# Beamersteuerung.net
KiCad netlist of a schematic drawn in EAGLE
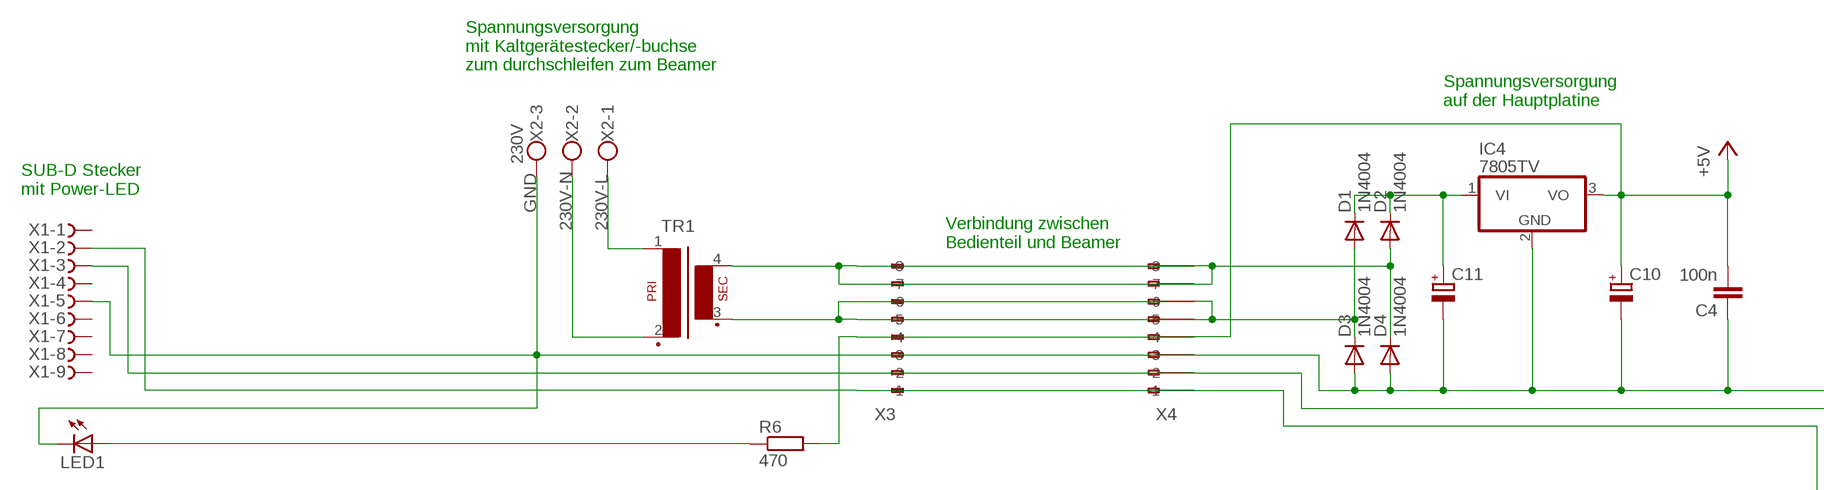
[diagram p0: schematic, sheet 1, part 1 of 2]
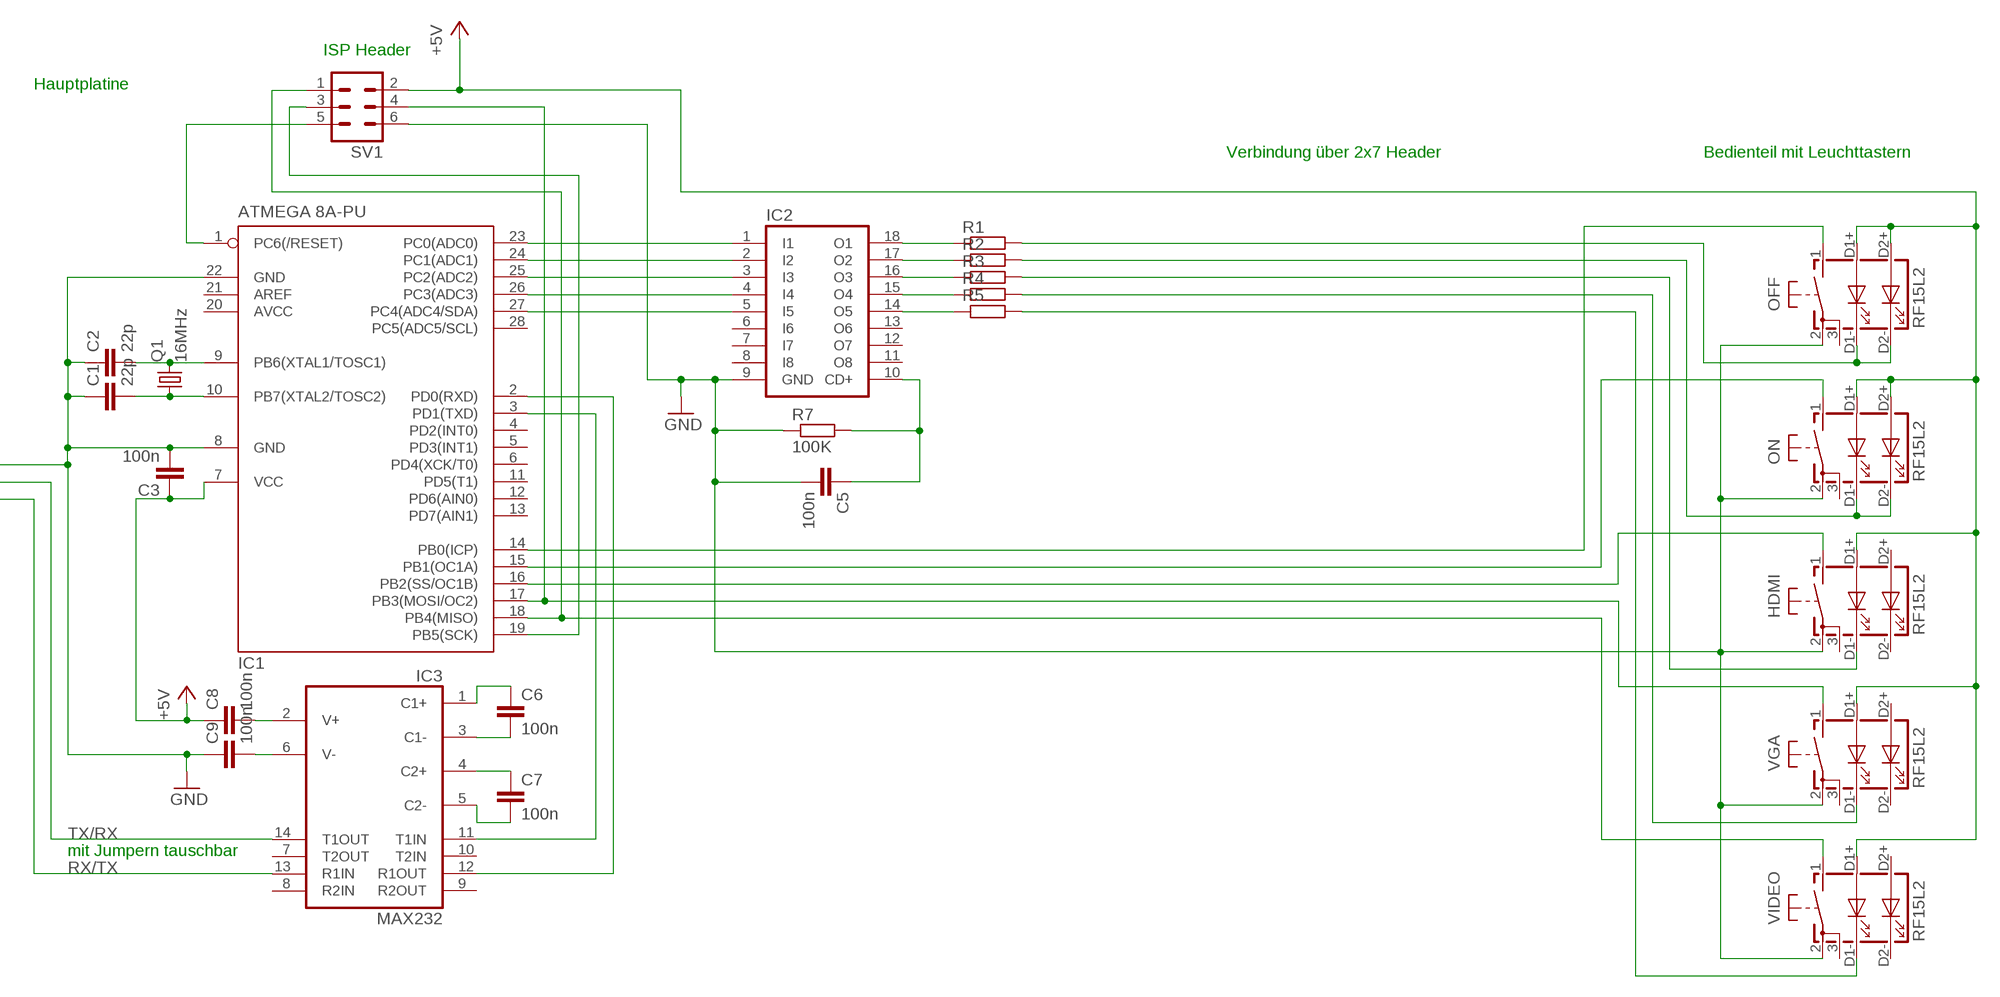
[diagram p1: schematic, sheet 1, part 2 of 2]

(export (version "E")
  (design (tool "Eeschema 10.0.6"))
  (components
    (comp (ref "C1")
      (value "22p")
      (footprint "eagle-import:C025-024X044")
      (libsource (lib "eagle-import") (part "C-EU025-024X044"))
    )
    (comp (ref "C2")
      (value "22p")
      (footprint "eagle-import:C025-024X044")
      (libsource (lib "eagle-import") (part "C-EU025-024X044"))
    )
    (comp (ref "C3")
      (value "100n")
      (footprint "eagle-import:C025-024X044")
      (libsource (lib "eagle-import") (part "C-EU025-024X044"))
    )
    (comp (ref "C4")
      (value "100n")
      (footprint "eagle-import:C025-024X044")
      (libsource (lib "eagle-import") (part "C-EU025-024X044"))
    )
    (comp (ref "C5")
      (value "100n")
      (footprint "eagle-import:C025-024X044")
      (libsource (lib "eagle-import") (part "C-EU025-024X044"))
    )
    (comp (ref "C6")
      (value "100n")
      (footprint "eagle-import:C025-024X044")
      (libsource (lib "eagle-import") (part "C-EU025-024X044"))
    )
    (comp (ref "C7")
      (value "100n")
      (footprint "eagle-import:C025-024X044")
      (libsource (lib "eagle-import") (part "C-EU025-024X044"))
    )
    (comp (ref "C8")
      (value "100n")
      (footprint "eagle-import:C025-024X044")
      (libsource (lib "eagle-import") (part "C-EU025-024X044"))
    )
    (comp (ref "C9")
      (value "100n")
      (footprint "eagle-import:C025-024X044")
      (libsource (lib "eagle-import") (part "C-EU025-024X044"))
    )
    (comp (ref "C10")
      (value "CPOL-EUE2.5-6")
      (footprint "eagle-import:E2,5-6")
      (libsource (lib "eagle-import") (part "CPOL-EUE2.5-6"))
    )
    (comp (ref "C11")
      (value "CPOL-EUE2.5-6")
      (footprint "eagle-import:E2,5-6")
      (libsource (lib "eagle-import") (part "CPOL-EUE2.5-6"))
    )
    (comp (ref "D1")
      (value "1N4004")
      (footprint "eagle-import:DO41-10")
      (libsource (lib "eagle-import") (part "1N4004"))
    )
    (comp (ref "D2")
      (value "1N4004")
      (footprint "eagle-import:DO41-10")
      (libsource (lib "eagle-import") (part "1N4004"))
    )
    (comp (ref "D3")
      (value "1N4004")
      (footprint "eagle-import:DO41-10")
      (libsource (lib "eagle-import") (part "1N4004"))
    )
    (comp (ref "D4")
      (value "1N4004")
      (footprint "eagle-import:DO41-10")
      (libsource (lib "eagle-import") (part "1N4004"))
    )
    (comp (ref "HDMI")
      (value "RF15L2")
      (footprint "eagle-import:RF15L2")
      (libsource (lib "eagle-import") (part "RF15L2"))
    )
    (comp (ref "IC1")
      (value "ATMEGA 8A-PU")
      (footprint "eagle-import:DIL28-3")
      (libsource (lib "eagle-import") (part "MEGA8-P"))
    )
    (comp (ref "IC2")
      (value "ULN2803A")
      (footprint "eagle-import:DIL18")
      (libsource (lib "eagle-import") (part "ULN2803A"))
    )
    (comp (ref "IC3")
      (value "MAX232")
      (footprint "eagle-import:DIL16")
      (fields (field (name "MF") "MAXIM") (field (name "MPN") "MAX232ACPE+"))
      (libsource (lib "eagle-import") (part "MAX232"))
    )
    (comp (ref "IC4")
      (value "7805TV")
      (footprint "eagle-import:TO220V")
      (libsource (lib "eagle-import") (part "78TV05"))
    )
    (comp (ref "LED1")
      (value "LED3MM")
      (footprint "eagle-import:LED3MM")
      (libsource (lib "eagle-import") (part "LED3MM"))
    )
    (comp (ref "OFF")
      (value "RF15L2")
      (footprint "eagle-import:RF15L2")
      (libsource (lib "eagle-import") (part "RF15L2"))
    )
    (comp (ref "ON")
      (value "RF15L2")
      (footprint "eagle-import:RF15L2")
      (libsource (lib "eagle-import") (part "RF15L2"))
    )
    (comp (ref "Q1")
      (value "16MHz")
      (footprint "eagle-import:HC49_S")
      (libsource (lib "eagle-import") (part "CRYSTALHC49S"))
    )
    (comp (ref "R1")
      (value "R-EU_0207/12")
      (footprint "eagle-import:0207_12")
      (libsource (lib "eagle-import") (part "R-EU_0207/12"))
    )
    (comp (ref "R2")
      (value "R-EU_0207/12")
      (footprint "eagle-import:0207_12")
      (libsource (lib "eagle-import") (part "R-EU_0207/12"))
    )
    (comp (ref "R3")
      (value "R-EU_0207/12")
      (footprint "eagle-import:0207_12")
      (libsource (lib "eagle-import") (part "R-EU_0207/12"))
    )
    (comp (ref "R4")
      (value "R-EU_0207/12")
      (footprint "eagle-import:0207_12")
      (libsource (lib "eagle-import") (part "R-EU_0207/12"))
    )
    (comp (ref "R5")
      (value "R-EU_0207/12")
      (footprint "eagle-import:0207_12")
      (libsource (lib "eagle-import") (part "R-EU_0207/12"))
    )
    (comp (ref "R6")
      (value "470")
      (footprint "eagle-import:0207_12")
      (libsource (lib "eagle-import") (part "R-EU_0207/12"))
    )
    (comp (ref "R7")
      (value "100K")
      (footprint "eagle-import:0207_12")
      (libsource (lib "eagle-import") (part "R-EU_0207/12"))
    )
    (comp (ref "SV1")
      (value "ML6")
      (footprint "eagle-import:ML6")
      (libsource (lib "eagle-import") (part "ML6"))
    )
    (comp (ref "TR1")
      (value "VP31")
      (footprint "eagle-import:VP31")
      (libsource (lib "eagle-import") (part "VP31"))
    )
    (comp (ref "VGA")
      (value "RF15L2")
      (footprint "eagle-import:RF15L2")
      (libsource (lib "eagle-import") (part "RF15L2"))
    )
    (comp (ref "VIDEO")
      (value "RF15L2")
      (footprint "eagle-import:RF15L2")
      (libsource (lib "eagle-import") (part "RF15L2"))
    )
    (comp (ref "X1")
      (value "F09VS")
      (footprint "eagle-import:F09V")
      (libsource (lib "eagle-import") (part "F09?SV"))
    )
    (comp (ref "X2")
      (value "230V")
      (footprint "eagle-import:W237-103")
      (fields (field (name "MPN") "237-103"))
      (libsource (lib "eagle-import") (part "W237-103"))
    )
    (comp (ref "X3")
      (value "233-508")
      (footprint "eagle-import:233-508")
      (fields (field (name "MF") "Wago Corporation") (field (name "MPN") "0233-0508"))
      (libsource (lib "eagle-import") (part "233-508"))
    )
    (comp (ref "X4")
      (value "233-508")
      (footprint "eagle-import:233-508")
      (fields (field (name "MF") "Wago Corporation") (field (name "MPN") "0233-0508"))
      (libsource (lib "eagle-import") (part "233-508"))
    )
  )
  (nets
    (net (code "1") (name "+5V") (class "Default")
      (node (ref "C10") (pin "+") (pinfunction "+_+") (pintype "passive"))
      (node (ref "C3") (pin "1") (pinfunction "1_1") (pintype "passive"))
      (node (ref "C4") (pin "2") (pinfunction "2_2") (pintype "passive"))
      (node (ref "C8") (pin "1") (pinfunction "1_1") (pintype "passive"))
      (node (ref "HDMI") (pin "D1+") (pinfunction "A1_D1+") (pintype "passive"))
      (node (ref "IC1") (pin "7") (pinfunction "VCC_7") (pintype "power_in"))
      (node (ref "IC4") (pin "3") (pinfunction "VO_3") (pintype "passive"))
      (node (ref "OFF") (pin "D1+") (pinfunction "A1_D1+") (pintype "passive"))
      (node (ref "OFF") (pin "D2+") (pinfunction "A2_D2+") (pintype "passive"))
      (node (ref "ON") (pin "D1+") (pinfunction "A1_D1+") (pintype "passive"))
      (node (ref "ON") (pin "D2+") (pinfunction "A2_D2+") (pintype "passive"))
      (node (ref "R6") (pin "2") (pinfunction "2_2") (pintype "passive"))
      (node (ref "SV1") (pin "2") (pinfunction "2_2") (pintype "passive"))
      (node (ref "VGA") (pin "D1+") (pinfunction "A1_D1+") (pintype "passive"))
      (node (ref "VIDEO") (pin "D1+") (pinfunction "A1_D1+") (pintype "passive"))
      (node (ref "X3") (pin "A4") (pinfunction "-4_A4") (pintype "passive"))
      (node (ref "X4") (pin "A4") (pinfunction "-4_A4") (pintype "passive"))
    )
    (net (code "2") (name "/230V-L") (class "Default")
      (node (ref "TR1") (pin "1") (pinfunction "P1_1") (pintype "passive"))
      (node (ref "X2") (pin "1") (pinfunction "KL_1") (pintype "passive"))
    )
    (net (code "3") (name "/230V-N") (class "Default")
      (node (ref "TR1") (pin "2") (pinfunction "P2_2") (pintype "passive"))
      (node (ref "X2") (pin "2") (pinfunction "KL_2") (pintype "passive"))
    )
    (net (code "4") (name "/AVCC") (class "Default")
      (node (ref "IC1") (pin "20") (pinfunction "AVCC_20") (pintype "power_in"))
    )
    (net (code "5") (name "/RX{slash}TX") (class "Default")
      (node (ref "IC3") (pin "13") (pinfunction "R1IN_13") (pintype "input"))
      (node (ref "X1") (pin "2") (pinfunction "F_2") (pintype "passive"))
      (node (ref "X3") (pin "A1") (pinfunction "-1_A1") (pintype "passive"))
      (node (ref "X4") (pin "A1") (pinfunction "-1_A1") (pintype "passive"))
    )
    (net (code "6") (name "/TX{slash}RX") (class "Default")
      (node (ref "IC3") (pin "14") (pinfunction "T1OUT_14") (pintype "output"))
      (node (ref "X1") (pin "3") (pinfunction "F_3") (pintype "passive"))
      (node (ref "X3") (pin "A2") (pinfunction "-2_A2") (pintype "passive"))
      (node (ref "X4") (pin "A2") (pinfunction "-2_A2") (pintype "passive"))
    )
    (net (code "7") (name "GND") (class "Default")
      (node (ref "C1") (pin "1") (pinfunction "1_1") (pintype "passive"))
      (node (ref "C10") (pin "-") (pinfunction "-_-") (pintype "passive"))
      (node (ref "C11") (pin "-") (pinfunction "-_-") (pintype "passive"))
      (node (ref "C2") (pin "1") (pinfunction "1_1") (pintype "passive"))
      (node (ref "C3") (pin "2") (pinfunction "2_2") (pintype "passive"))
      (node (ref "C4") (pin "1") (pinfunction "1_1") (pintype "passive"))
      (node (ref "C5") (pin "2") (pinfunction "2_2") (pintype "passive"))
      (node (ref "C9") (pin "1") (pinfunction "1_1") (pintype "passive"))
      (node (ref "D3") (pin "A") (pinfunction "A_A") (pintype "passive"))
      (node (ref "D4") (pin "A") (pinfunction "A_A") (pintype "passive"))
      (node (ref "HDMI") (pin "2") (pinfunction "P_2") (pintype "passive"))
      (node (ref "IC1") (pin "22") (pinfunction "GND_22") (pintype "power_in"))
      (node (ref "IC1") (pin "8") (pinfunction "GND_8") (pintype "power_in"))
      (node (ref "IC2") (pin "9") (pinfunction "GND_9") (pintype "power_in"))
      (node (ref "IC4") (pin "2") (pinfunction "GND_2") (pintype "passive"))
      (node (ref "LED1") (pin "K") (pinfunction "C_K") (pintype "passive"))
      (node (ref "OFF") (pin "2") (pinfunction "P_2") (pintype "passive"))
      (node (ref "ON") (pin "2") (pinfunction "P_2") (pintype "passive"))
      (node (ref "R7") (pin "1") (pinfunction "1_1") (pintype "passive"))
      (node (ref "SV1") (pin "6") (pinfunction "6_6") (pintype "passive"))
      (node (ref "VGA") (pin "2") (pinfunction "P_2") (pintype "passive"))
      (node (ref "VIDEO") (pin "2") (pinfunction "P_2") (pintype "passive"))
      (node (ref "X1") (pin "5") (pinfunction "F_5") (pintype "passive"))
      (node (ref "X2") (pin "3") (pinfunction "KL_3") (pintype "passive"))
      (node (ref "X3") (pin "A3") (pinfunction "-3_A3") (pintype "passive"))
      (node (ref "X4") (pin "A3") (pinfunction "-3_A3") (pintype "passive"))
    )
    (net (code "8") (name "Net-(HDMI-C1)") (class "Default")
      (node (ref "HDMI") (pin "D1-") (pinfunction "C1_D1-") (pintype "passive"))
      (node (ref "R3") (pin "2") (pinfunction "2_2") (pintype "passive"))
    )
    (net (code "9") (name "Net-(HDMI-S)") (class "Default")
      (node (ref "HDMI") (pin "1") (pinfunction "S_1") (pintype "passive"))
      (node (ref "IC1") (pin "16") (pinfunction "PB2(SS/OC1B)_16") (pintype "bidirectional"))
    )
    (net (code "10") (name "Net-(IC1-PB0(ICP))") (class "Default")
      (node (ref "IC1") (pin "14") (pinfunction "PB0(ICP)_14") (pintype "bidirectional"))
      (node (ref "OFF") (pin "1") (pinfunction "S_1") (pintype "passive"))
    )
    (net (code "11") (name "Net-(IC1-PB1(OC1A))") (class "Default")
      (node (ref "IC1") (pin "15") (pinfunction "PB1(OC1A)_15") (pintype "bidirectional"))
      (node (ref "ON") (pin "1") (pinfunction "S_1") (pintype "passive"))
    )
    (net (code "12") (name "Net-(IC1-PB3(MOSI{slash}OC2))") (class "Default")
      (node (ref "IC1") (pin "17") (pinfunction "PB3(MOSI/OC2)_17") (pintype "bidirectional"))
      (node (ref "SV1") (pin "4") (pinfunction "4_4") (pintype "passive"))
      (node (ref "VGA") (pin "1") (pinfunction "S_1") (pintype "passive"))
    )
    (net (code "13") (name "Net-(IC1-PB4(MISO))") (class "Default")
      (node (ref "IC1") (pin "18") (pinfunction "PB4(MISO)_18") (pintype "bidirectional"))
      (node (ref "SV1") (pin "1") (pinfunction "1_1") (pintype "passive"))
      (node (ref "VIDEO") (pin "1") (pinfunction "S_1") (pintype "passive"))
    )
    (net (code "14") (name "Net-(IC1-PB5(SCK))") (class "Default")
      (node (ref "IC1") (pin "19") (pinfunction "PB5(SCK)_19") (pintype "bidirectional"))
      (node (ref "SV1") (pin "3") (pinfunction "3_3") (pintype "passive"))
    )
    (net (code "15") (name "Net-(IC1-PB6(XTAL1{slash}TOSC1))") (class "Default")
      (node (ref "C2") (pin "2") (pinfunction "2_2") (pintype "passive"))
      (node (ref "IC1") (pin "9") (pinfunction "PB6(XTAL1/TOSC1)_9") (pintype "bidirectional"))
      (node (ref "Q1") (pin "2") (pinfunction "2_2") (pintype "passive"))
    )
    (net (code "16") (name "Net-(IC1-PB7(XTAL2{slash}TOSC2))") (class "Default")
      (node (ref "C1") (pin "2") (pinfunction "2_2") (pintype "passive"))
      (node (ref "IC1") (pin "10") (pinfunction "PB7(XTAL2/TOSC2)_10") (pintype "bidirectional"))
      (node (ref "Q1") (pin "1") (pinfunction "1_1") (pintype "passive"))
    )
    (net (code "17") (name "Net-(IC1-PC0(ADC0))") (class "Default")
      (node (ref "IC1") (pin "23") (pinfunction "PC0(ADC0)_23") (pintype "bidirectional"))
      (node (ref "IC2") (pin "1") (pinfunction "I1_1") (pintype "input"))
    )
    (net (code "18") (name "Net-(IC1-PC1(ADC1))") (class "Default")
      (node (ref "IC1") (pin "24") (pinfunction "PC1(ADC1)_24") (pintype "bidirectional"))
      (node (ref "IC2") (pin "2") (pinfunction "I2_2") (pintype "input"))
    )
    (net (code "19") (name "Net-(IC1-PC2(ADC2))") (class "Default")
      (node (ref "IC1") (pin "25") (pinfunction "PC2(ADC2)_25") (pintype "bidirectional"))
      (node (ref "IC2") (pin "3") (pinfunction "I3_3") (pintype "input"))
    )
    (net (code "20") (name "Net-(IC1-PC3(ADC3))") (class "Default")
      (node (ref "IC1") (pin "26") (pinfunction "PC3(ADC3)_26") (pintype "bidirectional"))
      (node (ref "IC2") (pin "4") (pinfunction "I4_4") (pintype "input"))
    )
    (net (code "21") (name "Net-(IC1-PC4(ADC4{slash}SDA))") (class "Default")
      (node (ref "IC1") (pin "27") (pinfunction "PC4(ADC4/SDA)_27") (pintype "bidirectional"))
      (node (ref "IC2") (pin "5") (pinfunction "I5_5") (pintype "input"))
    )
    (net (code "22") (name "Net-(IC1-PC6({slash}RESET))") (class "Default")
      (node (ref "IC1") (pin "1") (pinfunction "PC6(/RESET)_1") (pintype "bidirectional"))
      (node (ref "SV1") (pin "5") (pinfunction "5_5") (pintype "passive"))
    )
    (net (code "23") (name "Net-(IC1-PD0(RXD))") (class "Default")
      (node (ref "IC1") (pin "2") (pinfunction "PD0(RXD)_2") (pintype "bidirectional"))
      (node (ref "IC3") (pin "12") (pinfunction "R1OUT_12") (pintype "output"))
    )
    (net (code "24") (name "Net-(IC1-PD1(TXD))") (class "Default")
      (node (ref "IC1") (pin "3") (pinfunction "PD1(TXD)_3") (pintype "bidirectional"))
      (node (ref "IC3") (pin "11") (pinfunction "T1IN_11") (pintype "input"))
    )
    (net (code "25") (name "Net-(IC2-CD+)") (class "Default")
      (node (ref "C5") (pin "1") (pinfunction "1_1") (pintype "passive"))
      (node (ref "IC2") (pin "10") (pinfunction "CD+_10") (pintype "passive"))
      (node (ref "R7") (pin "2") (pinfunction "2_2") (pintype "passive"))
    )
    (net (code "26") (name "Net-(IC2-O1)") (class "Default")
      (node (ref "IC2") (pin "18") (pinfunction "O1_18") (pintype "open_collector"))
      (node (ref "R1") (pin "1") (pinfunction "1_1") (pintype "passive"))
    )
    (net (code "27") (name "Net-(IC2-O2)") (class "Default")
      (node (ref "IC2") (pin "17") (pinfunction "O2_17") (pintype "open_collector"))
      (node (ref "R2") (pin "1") (pinfunction "1_1") (pintype "passive"))
    )
    (net (code "28") (name "Net-(IC2-O3)") (class "Default")
      (node (ref "IC2") (pin "16") (pinfunction "O3_16") (pintype "open_collector"))
      (node (ref "R3") (pin "1") (pinfunction "1_1") (pintype "passive"))
    )
    (net (code "29") (name "Net-(IC2-O4)") (class "Default")
      (node (ref "IC2") (pin "15") (pinfunction "O4_15") (pintype "open_collector"))
      (node (ref "R4") (pin "1") (pinfunction "1_1") (pintype "passive"))
    )
    (net (code "30") (name "Net-(IC2-O5)") (class "Default")
      (node (ref "IC2") (pin "14") (pinfunction "O5_14") (pintype "open_collector"))
      (node (ref "R5") (pin "1") (pinfunction "1_1") (pintype "passive"))
    )
    (net (code "31") (name "Net-(IC3A-C1+)") (class "Default")
      (node (ref "C6") (pin "1") (pinfunction "1_1") (pintype "passive"))
      (node (ref "IC3") (pin "1") (pinfunction "C1+_1") (pintype "bidirectional"))
    )
    (net (code "32") (name "Net-(IC3A-C1-)") (class "Default")
      (node (ref "C6") (pin "2") (pinfunction "2_2") (pintype "passive"))
      (node (ref "IC3") (pin "3") (pinfunction "C1-_3") (pintype "bidirectional"))
    )
    (net (code "33") (name "Net-(IC3A-C2+)") (class "Default")
      (node (ref "C7") (pin "1") (pinfunction "1_1") (pintype "passive"))
      (node (ref "IC3") (pin "4") (pinfunction "C2+_4") (pintype "bidirectional"))
    )
    (net (code "34") (name "Net-(IC3A-C2-)") (class "Default")
      (node (ref "C7") (pin "2") (pinfunction "2_2") (pintype "passive"))
      (node (ref "IC3") (pin "5") (pinfunction "C2-_5") (pintype "bidirectional"))
    )
    (net (code "35") (name "Net-(IC3A-V+)") (class "Default")
      (node (ref "C8") (pin "2") (pinfunction "2_2") (pintype "passive"))
      (node (ref "IC3") (pin "2") (pinfunction "V+_2") (pintype "bidirectional"))
    )
    (net (code "36") (name "Net-(IC3A-V-)") (class "Default")
      (node (ref "C9") (pin "2") (pinfunction "2_2") (pintype "passive"))
      (node (ref "IC3") (pin "6") (pinfunction "V-_6") (pintype "bidirectional"))
    )
    (net (code "37") (name "Net-(IC4-VI)") (class "Default")
      (node (ref "C11") (pin "+") (pinfunction "+_+") (pintype "passive"))
      (node (ref "D1") (pin "C") (pinfunction "C_C") (pintype "passive"))
      (node (ref "D2") (pin "C") (pinfunction "C_C") (pintype "passive"))
      (node (ref "IC4") (pin "1") (pinfunction "VI_1") (pintype "input"))
    )
    (net (code "38") (name "Net-(LED1-PadA)") (class "Default")
      (node (ref "LED1") (pin "A") (pinfunction "A_A") (pintype "passive"))
      (node (ref "R6") (pin "1") (pinfunction "1_1") (pintype "passive"))
    )
    (net (code "39") (name "Net-(OFF-C1)") (class "Default")
      (node (ref "OFF") (pin "D1-") (pinfunction "C1_D1-") (pintype "passive"))
      (node (ref "OFF") (pin "D2-") (pinfunction "C2_D2-") (pintype "passive"))
      (node (ref "R1") (pin "2") (pinfunction "2_2") (pintype "passive"))
    )
    (net (code "40") (name "Net-(ON-C1)") (class "Default")
      (node (ref "ON") (pin "D1-") (pinfunction "C1_D1-") (pintype "passive"))
      (node (ref "ON") (pin "D2-") (pinfunction "C2_D2-") (pintype "passive"))
      (node (ref "R2") (pin "2") (pinfunction "2_2") (pintype "passive"))
    )
    (net (code "41") (name "Net-(TR1-S3)") (class "Default")
      (node (ref "D1") (pin "A") (pinfunction "A_A") (pintype "passive"))
      (node (ref "D3") (pin "C") (pinfunction "C_C") (pintype "passive"))
      (node (ref "TR1") (pin "3") (pinfunction "S3_3") (pintype "passive"))
      (node (ref "X3") (pin "A5") (pinfunction "-5_A5") (pintype "passive"))
      (node (ref "X3") (pin "A6") (pinfunction "-6_A6") (pintype "passive"))
      (node (ref "X4") (pin "A5") (pinfunction "-5_A5") (pintype "passive"))
      (node (ref "X4") (pin "A6") (pinfunction "-6_A6") (pintype "passive"))
    )
    (net (code "42") (name "Net-(TR1-S4)") (class "Default")
      (node (ref "D2") (pin "A") (pinfunction "A_A") (pintype "passive"))
      (node (ref "D4") (pin "C") (pinfunction "C_C") (pintype "passive"))
      (node (ref "TR1") (pin "4") (pinfunction "S4_4") (pintype "passive"))
      (node (ref "X3") (pin "A7") (pinfunction "-7_A7") (pintype "passive"))
      (node (ref "X3") (pin "A8") (pinfunction "-8_A8") (pintype "passive"))
      (node (ref "X4") (pin "A7") (pinfunction "-7_A7") (pintype "passive"))
      (node (ref "X4") (pin "A8") (pinfunction "-8_A8") (pintype "passive"))
    )
    (net (code "43") (name "Net-(VGA-C1)") (class "Default")
      (node (ref "R4") (pin "2") (pinfunction "2_2") (pintype "passive"))
      (node (ref "VGA") (pin "D1-") (pinfunction "C1_D1-") (pintype "passive"))
    )
    (net (code "44") (name "Net-(VIDEO-C1)") (class "Default")
      (node (ref "R5") (pin "2") (pinfunction "2_2") (pintype "passive"))
      (node (ref "VIDEO") (pin "D1-") (pinfunction "C1_D1-") (pintype "passive"))
    )
    (net (code "45") (name "unconnected-(HDMI-A2-PadD2+)") (class "Default")
      (node (ref "HDMI") (pin "D2+") (pinfunction "A2_D2+") (pintype "passive"))
    )
    (net (code "46") (name "unconnected-(HDMI-C2-PadD2-)") (class "Default")
      (node (ref "HDMI") (pin "D2-") (pinfunction "C2_D2-") (pintype "passive"))
    )
    (net (code "47") (name "unconnected-(HDMI-P-Pad3)") (class "Default")
      (node (ref "HDMI") (pin "3") (pinfunction "P_3") (pintype "passive"))
    )
    (net (code "48") (name "unconnected-(IC1-AREF-Pad21)") (class "Default")
      (node (ref "IC1") (pin "21") (pinfunction "AREF_21") (pintype "passive"))
    )
    (net (code "49") (name "unconnected-(IC1-PC5(ADC5{slash}SCL)-Pad28)") (class "Default")
      (node (ref "IC1") (pin "28") (pinfunction "PC5(ADC5/SCL)_28") (pintype "bidirectional"))
    )
    (net (code "50") (name "unconnected-(IC1-PD2(INT0)-Pad4)") (class "Default")
      (node (ref "IC1") (pin "4") (pinfunction "PD2(INT0)_4") (pintype "bidirectional"))
    )
    (net (code "51") (name "unconnected-(IC1-PD3(INT1)-Pad5)") (class "Default")
      (node (ref "IC1") (pin "5") (pinfunction "PD3(INT1)_5") (pintype "bidirectional"))
    )
    (net (code "52") (name "unconnected-(IC1-PD4(XCK{slash}T0)-Pad6)") (class "Default")
      (node (ref "IC1") (pin "6") (pinfunction "PD4(XCK/T0)_6") (pintype "bidirectional"))
    )
    (net (code "53") (name "unconnected-(IC1-PD5(T1)-Pad11)") (class "Default")
      (node (ref "IC1") (pin "11") (pinfunction "PD5(T1)_11") (pintype "bidirectional"))
    )
    (net (code "54") (name "unconnected-(IC1-PD6(AIN0)-Pad12)") (class "Default")
      (node (ref "IC1") (pin "12") (pinfunction "PD6(AIN0)_12") (pintype "bidirectional"))
    )
    (net (code "55") (name "unconnected-(IC1-PD7(AIN1)-Pad13)") (class "Default")
      (node (ref "IC1") (pin "13") (pinfunction "PD7(AIN1)_13") (pintype "bidirectional"))
    )
    (net (code "56") (name "unconnected-(IC2-I6-Pad6)") (class "Default")
      (node (ref "IC2") (pin "6") (pinfunction "I6_6") (pintype "input"))
    )
    (net (code "57") (name "unconnected-(IC2-I7-Pad7)") (class "Default")
      (node (ref "IC2") (pin "7") (pinfunction "I7_7") (pintype "input"))
    )
    (net (code "58") (name "unconnected-(IC2-I8-Pad8)") (class "Default")
      (node (ref "IC2") (pin "8") (pinfunction "I8_8") (pintype "input"))
    )
    (net (code "59") (name "unconnected-(IC2-O6-Pad13)") (class "Default")
      (node (ref "IC2") (pin "13") (pinfunction "O6_13") (pintype "open_collector"))
    )
    (net (code "60") (name "unconnected-(IC2-O7-Pad12)") (class "Default")
      (node (ref "IC2") (pin "12") (pinfunction "O7_12") (pintype "open_collector"))
    )
    (net (code "61") (name "unconnected-(IC2-O8-Pad11)") (class "Default")
      (node (ref "IC2") (pin "11") (pinfunction "O8_11") (pintype "open_collector"))
    )
    (net (code "62") (name "unconnected-(IC3A-R2IN-Pad8)") (class "Default")
      (node (ref "IC3") (pin "8") (pinfunction "R2IN_8") (pintype "input"))
    )
    (net (code "63") (name "unconnected-(IC3A-R2OUT-Pad9)") (class "Default")
      (node (ref "IC3") (pin "9") (pinfunction "R2OUT_9") (pintype "output"))
    )
    (net (code "64") (name "unconnected-(IC3A-T2IN-Pad10)") (class "Default")
      (node (ref "IC3") (pin "10") (pinfunction "T2IN_10") (pintype "input"))
    )
    (net (code "65") (name "unconnected-(IC3A-T2OUT-Pad7)") (class "Default")
      (node (ref "IC3") (pin "7") (pinfunction "T2OUT_7") (pintype "output"))
    )
    (net (code "66") (name "unconnected-(OFF-P-Pad3)") (class "Default")
      (node (ref "OFF") (pin "3") (pinfunction "P_3") (pintype "passive"))
    )
    (net (code "67") (name "unconnected-(ON-P-Pad3)") (class "Default")
      (node (ref "ON") (pin "3") (pinfunction "P_3") (pintype "passive"))
    )
    (net (code "68") (name "unconnected-(VGA-A2-PadD2+)") (class "Default")
      (node (ref "VGA") (pin "D2+") (pinfunction "A2_D2+") (pintype "passive"))
    )
    (net (code "69") (name "unconnected-(VGA-C2-PadD2-)") (class "Default")
      (node (ref "VGA") (pin "D2-") (pinfunction "C2_D2-") (pintype "passive"))
    )
    (net (code "70") (name "unconnected-(VGA-P-Pad3)") (class "Default")
      (node (ref "VGA") (pin "3") (pinfunction "P_3") (pintype "passive"))
    )
    (net (code "71") (name "unconnected-(VIDEO-A2-PadD2+)") (class "Default")
      (node (ref "VIDEO") (pin "D2+") (pinfunction "A2_D2+") (pintype "passive"))
    )
    (net (code "72") (name "unconnected-(VIDEO-C2-PadD2-)") (class "Default")
      (node (ref "VIDEO") (pin "D2-") (pinfunction "C2_D2-") (pintype "passive"))
    )
    (net (code "73") (name "unconnected-(VIDEO-P-Pad3)") (class "Default")
      (node (ref "VIDEO") (pin "3") (pinfunction "P_3") (pintype "passive"))
    )
    (net (code "74") (name "unconnected-(X1A-F-Pad1)") (class "Default")
      (node (ref "X1") (pin "1") (pinfunction "F_1") (pintype "passive"))
    )
    (net (code "75") (name "unconnected-(X1D-F-Pad4)") (class "Default")
      (node (ref "X1") (pin "4") (pinfunction "F_4") (pintype "passive"))
    )
    (net (code "76") (name "unconnected-(X1F-F-Pad6)") (class "Default")
      (node (ref "X1") (pin "6") (pinfunction "F_6") (pintype "passive"))
    )
    (net (code "77") (name "unconnected-(X1G-F-Pad7)") (class "Default")
      (node (ref "X1") (pin "7") (pinfunction "F_7") (pintype "passive"))
    )
    (net (code "78") (name "unconnected-(X1H-F-Pad8)") (class "Default")
      (node (ref "X1") (pin "8") (pinfunction "F_8") (pintype "passive"))
    )
    (net (code "79") (name "unconnected-(X1I-F-Pad9)") (class "Default")
      (node (ref "X1") (pin "9") (pinfunction "F_9") (pintype "passive"))
    )
    (net (code "80") (name "unconnected-(X3-B-1-PadB1)") (class "Default")
      (node (ref "X3") (pin "B1") (pinfunction "B-1_B1") (pintype "passive"))
    )
    (net (code "81") (name "unconnected-(X3-B-2-PadB2)") (class "Default")
      (node (ref "X3") (pin "B2") (pinfunction "B-2_B2") (pintype "passive"))
    )
    (net (code "82") (name "unconnected-(X3-B-3-PadB3)") (class "Default")
      (node (ref "X3") (pin "B3") (pinfunction "B-3_B3") (pintype "passive"))
    )
    (net (code "83") (name "unconnected-(X3-B-4-PadB4)") (class "Default")
      (node (ref "X3") (pin "B4") (pinfunction "B-4_B4") (pintype "passive"))
    )
    (net (code "84") (name "unconnected-(X3-B-5-PadB5)") (class "Default")
      (node (ref "X3") (pin "B5") (pinfunction "B-5_B5") (pintype "passive"))
    )
    (net (code "85") (name "unconnected-(X3-B-6-PadB6)") (class "Default")
      (node (ref "X3") (pin "B6") (pinfunction "B-6_B6") (pintype "passive"))
    )
    (net (code "86") (name "unconnected-(X3-B-7-PadB7)") (class "Default")
      (node (ref "X3") (pin "B7") (pinfunction "B-7_B7") (pintype "passive"))
    )
    (net (code "87") (name "unconnected-(X3-B-8-PadB8)") (class "Default")
      (node (ref "X3") (pin "B8") (pinfunction "B-8_B8") (pintype "passive"))
    )
    (net (code "88") (name "unconnected-(X4-B-1-PadB1)") (class "Default")
      (node (ref "X4") (pin "B1") (pinfunction "B-1_B1") (pintype "passive"))
    )
    (net (code "89") (name "unconnected-(X4-B-2-PadB2)") (class "Default")
      (node (ref "X4") (pin "B2") (pinfunction "B-2_B2") (pintype "passive"))
    )
    (net (code "90") (name "unconnected-(X4-B-3-PadB3)") (class "Default")
      (node (ref "X4") (pin "B3") (pinfunction "B-3_B3") (pintype "passive"))
    )
    (net (code "91") (name "unconnected-(X4-B-4-PadB4)") (class "Default")
      (node (ref "X4") (pin "B4") (pinfunction "B-4_B4") (pintype "passive"))
    )
    (net (code "92") (name "unconnected-(X4-B-5-PadB5)") (class "Default")
      (node (ref "X4") (pin "B5") (pinfunction "B-5_B5") (pintype "passive"))
    )
    (net (code "93") (name "unconnected-(X4-B-6-PadB6)") (class "Default")
      (node (ref "X4") (pin "B6") (pinfunction "B-6_B6") (pintype "passive"))
    )
    (net (code "94") (name "unconnected-(X4-B-7-PadB7)") (class "Default")
      (node (ref "X4") (pin "B7") (pinfunction "B-7_B7") (pintype "passive"))
    )
    (net (code "95") (name "unconnected-(X4-B-8-PadB8)") (class "Default")
      (node (ref "X4") (pin "B8") (pinfunction "B-8_B8") (pintype "passive"))
    )
  )
)
